# prob.net
KiCad netlist of a schematic drawn in EasyEDA
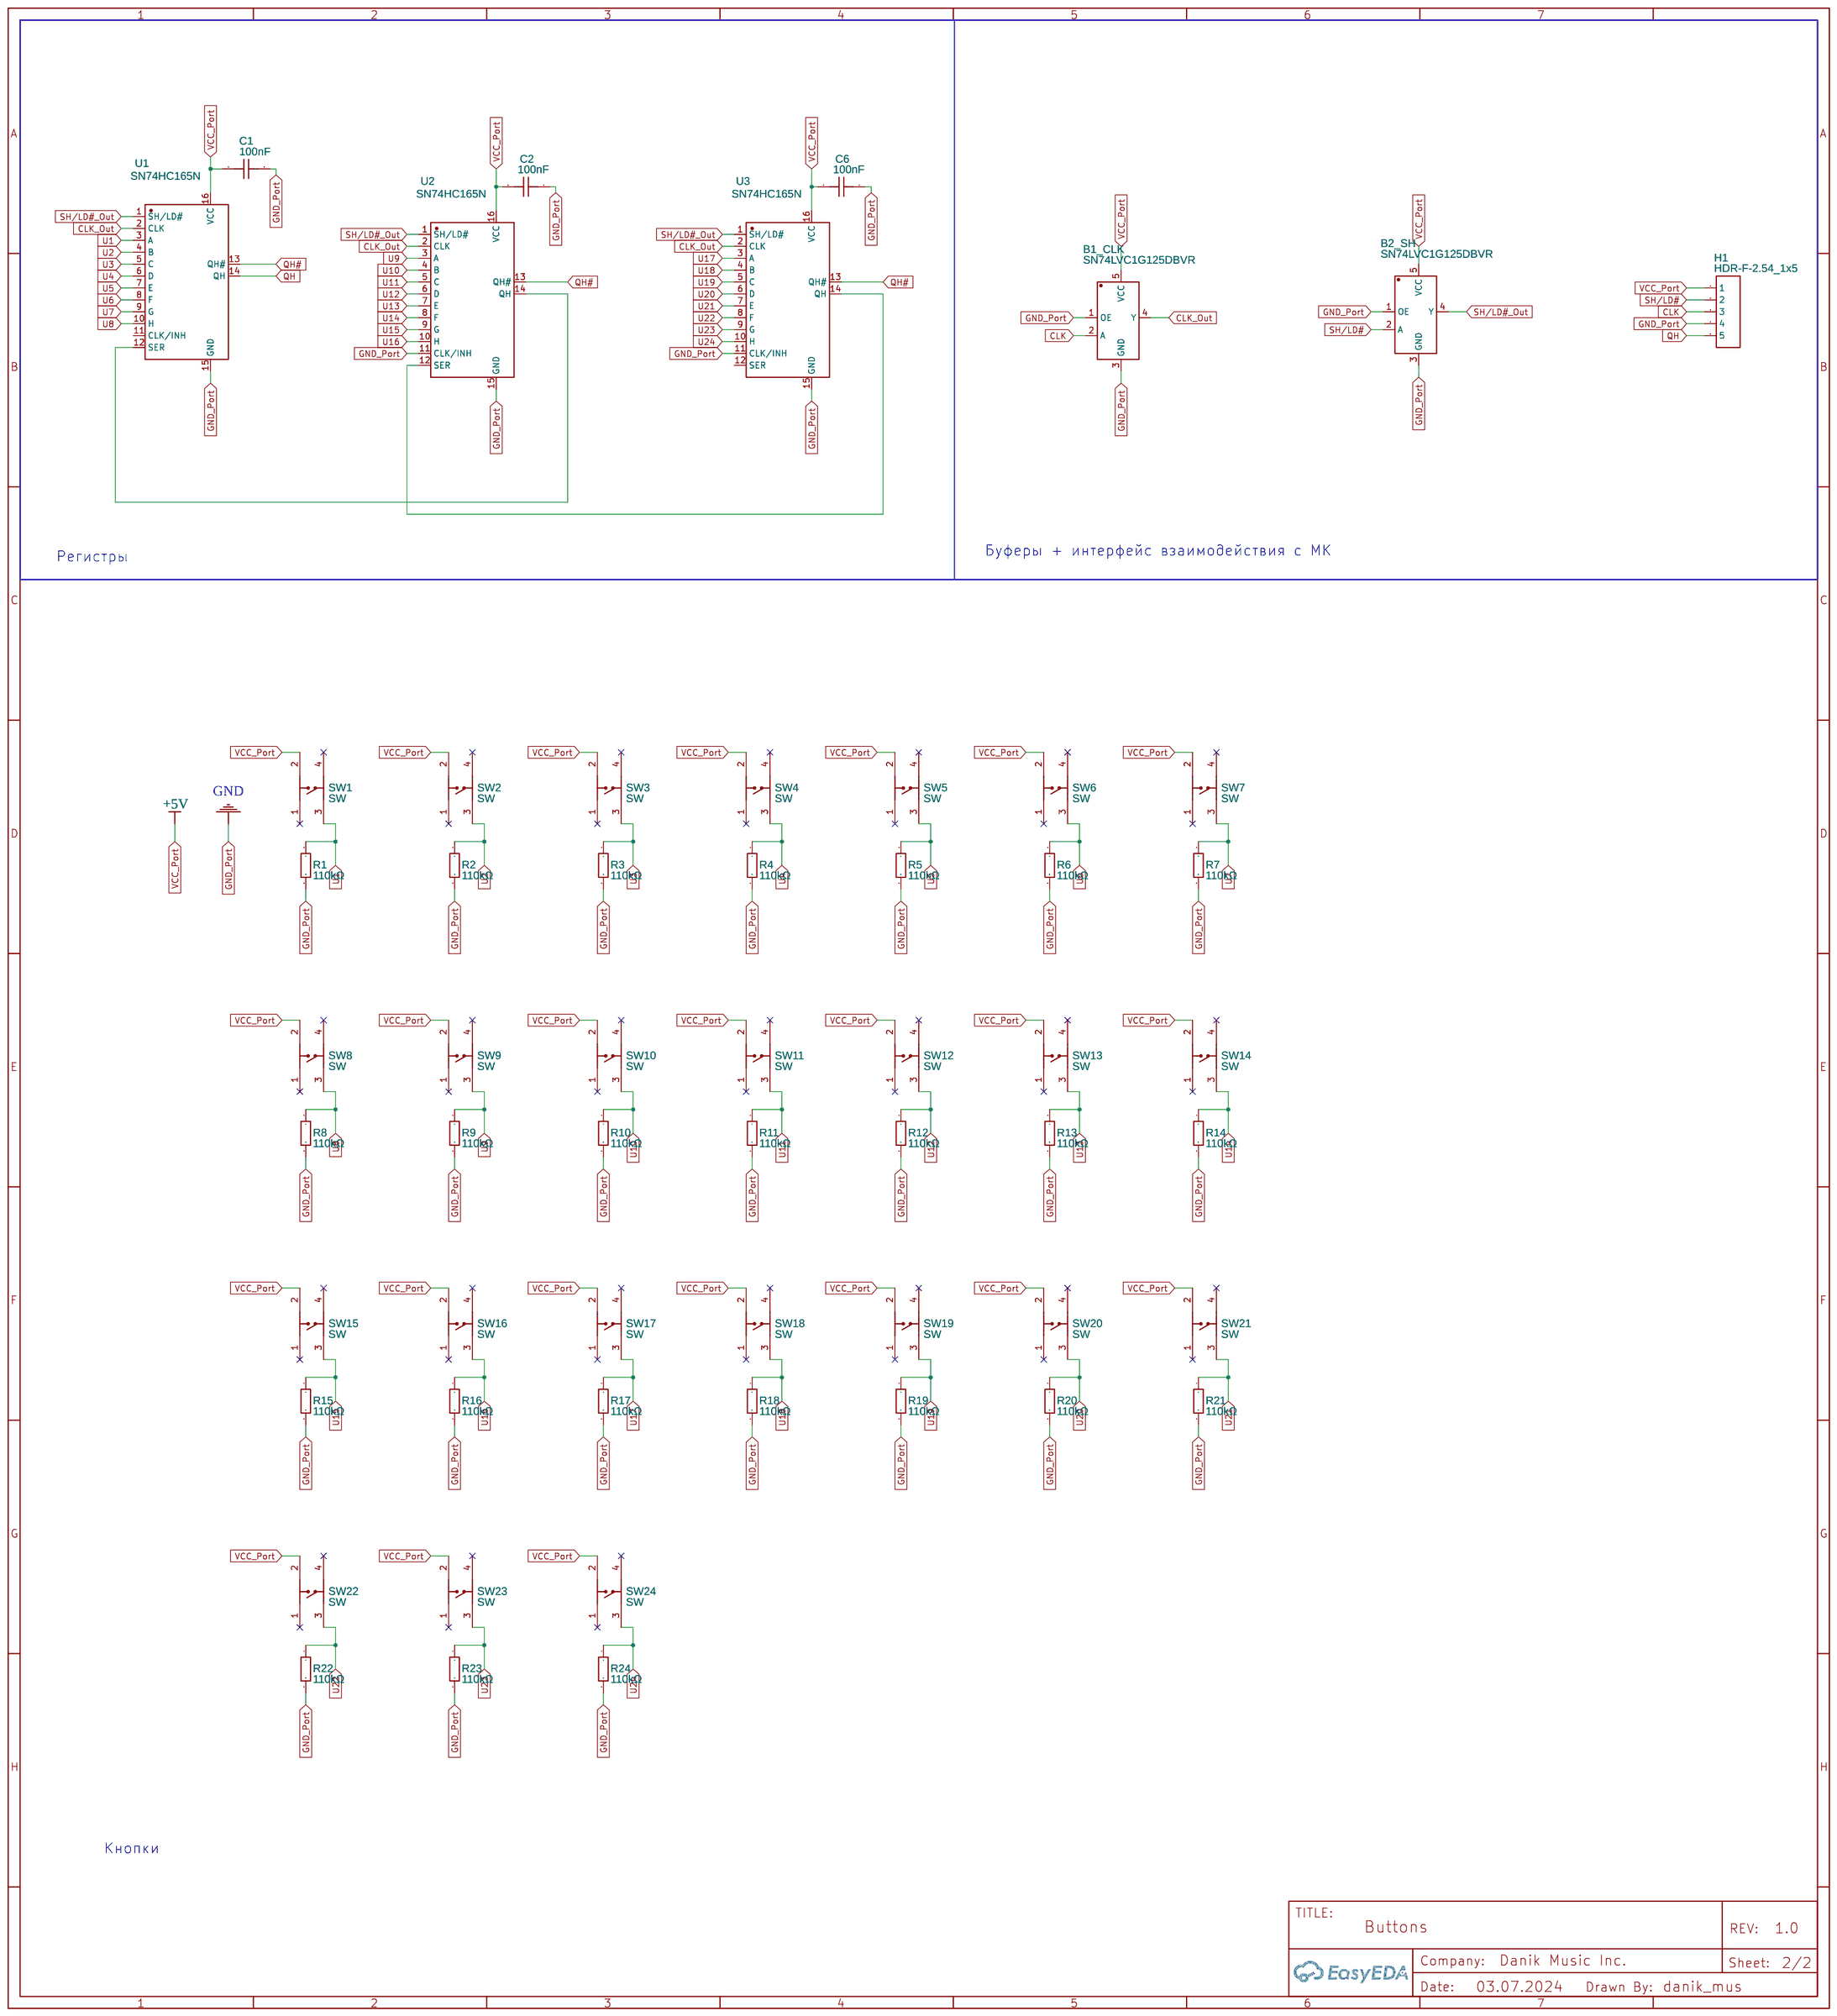
[diagram p0: schematic sheet]

(export (version "E")
  (design (tool "Eeschema 10.0.6"))
  (components
    (comp (ref "B1_CLK")
      (value "SN74LVC1G125DBVR")
      (fields (field (name "Manufacturer") "TI(德州仪器)"))
      (libsource (lib "") (part "SN74LVC1G125DBVR"))
    )
    (comp (ref "B2_SH")
      (value "SN74LVC1G125DBVR")
      (fields (field (name "Manufacturer") "TI(德州仪器)"))
      (libsource (lib "") (part "SN74LVC1G125DBVR_1"))
    )
    (comp (ref "C1")
      (value "100nF")
      (fields (field (name "Manufacturer Part") "PE104J2A0504") (field (name "Manufacturer") "KYET(科雅)"))
      (libsource (lib "") (part "PE104J2A0504_1"))
    )
    (comp (ref "C2")
      (value "100nF")
      (fields (field (name "Manufacturer Part") "PE104J2A0504") (field (name "Manufacturer") "KYET(科雅)"))
      (libsource (lib "") (part "PE104J2A0504"))
    )
    (comp (ref "C6")
      (value "100nF")
      (fields (field (name "Manufacturer Part") "PE104J2A0504") (field (name "Manufacturer") "KYET(科雅)"))
      (libsource (lib "") (part "PE104J2A0504"))
    )
    (comp (ref "H1") (value "HDR-F-2.54_1x5") (libsource (lib "") (part "HDR-F-2.54_1x5")))
    (comp (ref "R1")
      (value "110kΩ")
      (fields
        (field (name "Manufacturer Part") "CF1/4W-110KΩ±5% T52")
        (field (name "Manufacturer") "CCO(千志电子)")
      )
      (libsource (lib "") (part "CF1/4W-110KΩ±5% T52"))
    )
    (comp (ref "R2")
      (value "110kΩ")
      (fields
        (field (name "Manufacturer Part") "CF1/4W-110KΩ±5% T52")
        (field (name "Manufacturer") "CCO(千志电子)")
      )
      (libsource (lib "") (part "CF1/4W-110KΩ±5% T52"))
    )
    (comp (ref "R3")
      (value "110kΩ")
      (fields
        (field (name "Manufacturer Part") "CF1/4W-110KΩ±5% T52")
        (field (name "Manufacturer") "CCO(千志电子)")
      )
      (libsource (lib "") (part "CF1/4W-110KΩ±5% T52"))
    )
    (comp (ref "R4")
      (value "110kΩ")
      (fields
        (field (name "Manufacturer Part") "CF1/4W-110KΩ±5% T52")
        (field (name "Manufacturer") "CCO(千志电子)")
      )
      (libsource (lib "") (part "CF1/4W-110KΩ±5% T52"))
    )
    (comp (ref "R5")
      (value "110kΩ")
      (fields
        (field (name "Manufacturer Part") "CF1/4W-110KΩ±5% T52")
        (field (name "Manufacturer") "CCO(千志电子)")
      )
      (libsource (lib "") (part "CF1/4W-110KΩ±5% T52"))
    )
    (comp (ref "R6")
      (value "110kΩ")
      (fields
        (field (name "Manufacturer Part") "CF1/4W-110KΩ±5% T52")
        (field (name "Manufacturer") "CCO(千志电子)")
      )
      (libsource (lib "") (part "CF1/4W-110KΩ±5% T52"))
    )
    (comp (ref "R7")
      (value "110kΩ")
      (fields
        (field (name "Manufacturer Part") "CF1/4W-110KΩ±5% T52")
        (field (name "Manufacturer") "CCO(千志电子)")
      )
      (libsource (lib "") (part "CF1/4W-110KΩ±5% T52"))
    )
    (comp (ref "R8")
      (value "110kΩ")
      (fields
        (field (name "Manufacturer Part") "CF1/4W-110KΩ±5% T52")
        (field (name "Manufacturer") "CCO(千志电子)")
      )
      (libsource (lib "") (part "CF1/4W-110KΩ±5% T52"))
    )
    (comp (ref "R9")
      (value "110kΩ")
      (fields
        (field (name "Manufacturer Part") "CF1/4W-110KΩ±5% T52")
        (field (name "Manufacturer") "CCO(千志电子)")
      )
      (libsource (lib "") (part "CF1/4W-110KΩ±5% T52"))
    )
    (comp (ref "R10")
      (value "110kΩ")
      (fields
        (field (name "Manufacturer Part") "CF1/4W-110KΩ±5% T52")
        (field (name "Manufacturer") "CCO(千志电子)")
      )
      (libsource (lib "") (part "CF1/4W-110KΩ±5% T52"))
    )
    (comp (ref "R11")
      (value "110kΩ")
      (fields
        (field (name "Manufacturer Part") "CF1/4W-110KΩ±5% T52")
        (field (name "Manufacturer") "CCO(千志电子)")
      )
      (libsource (lib "") (part "CF1/4W-110KΩ±5% T52"))
    )
    (comp (ref "R12")
      (value "110kΩ")
      (fields
        (field (name "Manufacturer Part") "CF1/4W-110KΩ±5% T52")
        (field (name "Manufacturer") "CCO(千志电子)")
      )
      (libsource (lib "") (part "CF1/4W-110KΩ±5% T52"))
    )
    (comp (ref "R13")
      (value "110kΩ")
      (fields
        (field (name "Manufacturer Part") "CF1/4W-110KΩ±5% T52")
        (field (name "Manufacturer") "CCO(千志电子)")
      )
      (libsource (lib "") (part "CF1/4W-110KΩ±5% T52"))
    )
    (comp (ref "R14")
      (value "110kΩ")
      (fields
        (field (name "Manufacturer Part") "CF1/4W-110KΩ±5% T52")
        (field (name "Manufacturer") "CCO(千志电子)")
      )
      (libsource (lib "") (part "CF1/4W-110KΩ±5% T52"))
    )
    (comp (ref "R15")
      (value "110kΩ")
      (fields
        (field (name "Manufacturer Part") "CF1/4W-110KΩ±5% T52")
        (field (name "Manufacturer") "CCO(千志电子)")
      )
      (libsource (lib "") (part "CF1/4W-110KΩ±5% T52"))
    )
    (comp (ref "R16")
      (value "110kΩ")
      (fields
        (field (name "Manufacturer Part") "CF1/4W-110KΩ±5% T52")
        (field (name "Manufacturer") "CCO(千志电子)")
      )
      (libsource (lib "") (part "CF1/4W-110KΩ±5% T52"))
    )
    (comp (ref "R17")
      (value "110kΩ")
      (fields
        (field (name "Manufacturer Part") "CF1/4W-110KΩ±5% T52")
        (field (name "Manufacturer") "CCO(千志电子)")
      )
      (libsource (lib "") (part "CF1/4W-110KΩ±5% T52"))
    )
    (comp (ref "R18")
      (value "110kΩ")
      (fields
        (field (name "Manufacturer Part") "CF1/4W-110KΩ±5% T52")
        (field (name "Manufacturer") "CCO(千志电子)")
      )
      (libsource (lib "") (part "CF1/4W-110KΩ±5% T52"))
    )
    (comp (ref "R19")
      (value "110kΩ")
      (fields
        (field (name "Manufacturer Part") "CF1/4W-110KΩ±5% T52")
        (field (name "Manufacturer") "CCO(千志电子)")
      )
      (libsource (lib "") (part "CF1/4W-110KΩ±5% T52"))
    )
    (comp (ref "R20")
      (value "110kΩ")
      (fields
        (field (name "Manufacturer Part") "CF1/4W-110KΩ±5% T52")
        (field (name "Manufacturer") "CCO(千志电子)")
      )
      (libsource (lib "") (part "CF1/4W-110KΩ±5% T52"))
    )
    (comp (ref "R21")
      (value "110kΩ")
      (fields
        (field (name "Manufacturer Part") "CF1/4W-110KΩ±5% T52")
        (field (name "Manufacturer") "CCO(千志电子)")
      )
      (libsource (lib "") (part "CF1/4W-110KΩ±5% T52"))
    )
    (comp (ref "R22")
      (value "110kΩ")
      (fields
        (field (name "Manufacturer Part") "CF1/4W-110KΩ±5% T52")
        (field (name "Manufacturer") "CCO(千志电子)")
      )
      (libsource (lib "") (part "CF1/4W-110KΩ±5% T52"))
    )
    (comp (ref "R23")
      (value "110kΩ")
      (fields
        (field (name "Manufacturer Part") "CF1/4W-110KΩ±5% T52")
        (field (name "Manufacturer") "CCO(千志电子)")
      )
      (libsource (lib "") (part "CF1/4W-110KΩ±5% T52"))
    )
    (comp (ref "R24")
      (value "110kΩ")
      (fields
        (field (name "Manufacturer Part") "CF1/4W-110KΩ±5% T52")
        (field (name "Manufacturer") "CCO(千志电子)")
      )
      (libsource (lib "") (part "CF1/4W-110KΩ±5% T52"))
    )
    (comp (ref "SW1")
      (value "SW")
      (fields (field (name "Manufacturer Part") "按键"))
      (libsource (lib "") (part "SW"))
    )
    (comp (ref "SW2")
      (value "SW")
      (fields (field (name "Manufacturer Part") "按键"))
      (libsource (lib "") (part "SW"))
    )
    (comp (ref "SW3")
      (value "SW")
      (fields (field (name "Manufacturer Part") "按键"))
      (libsource (lib "") (part "SW"))
    )
    (comp (ref "SW4")
      (value "SW")
      (fields (field (name "Manufacturer Part") "按键"))
      (libsource (lib "") (part "SW"))
    )
    (comp (ref "SW5")
      (value "SW")
      (fields (field (name "Manufacturer Part") "按键"))
      (libsource (lib "") (part "SW"))
    )
    (comp (ref "SW6")
      (value "SW")
      (fields (field (name "Manufacturer Part") "按键"))
      (libsource (lib "") (part "SW"))
    )
    (comp (ref "SW7")
      (value "SW")
      (fields (field (name "Manufacturer Part") "按键"))
      (libsource (lib "") (part "SW"))
    )
    (comp (ref "SW8")
      (value "SW")
      (fields (field (name "Manufacturer Part") "按键"))
      (libsource (lib "") (part "SW"))
    )
    (comp (ref "SW9")
      (value "SW")
      (fields (field (name "Manufacturer Part") "按键"))
      (libsource (lib "") (part "SW"))
    )
    (comp (ref "SW10")
      (value "SW")
      (fields (field (name "Manufacturer Part") "按键"))
      (libsource (lib "") (part "SW"))
    )
    (comp (ref "SW11")
      (value "SW")
      (fields (field (name "Manufacturer Part") "按键"))
      (libsource (lib "") (part "SW"))
    )
    (comp (ref "SW12")
      (value "SW")
      (fields (field (name "Manufacturer Part") "按键"))
      (libsource (lib "") (part "SW"))
    )
    (comp (ref "SW13")
      (value "SW")
      (fields (field (name "Manufacturer Part") "按键"))
      (libsource (lib "") (part "SW"))
    )
    (comp (ref "SW14")
      (value "SW")
      (fields (field (name "Manufacturer Part") "按键"))
      (libsource (lib "") (part "SW"))
    )
    (comp (ref "SW15")
      (value "SW")
      (fields (field (name "Manufacturer Part") "按键"))
      (libsource (lib "") (part "SW"))
    )
    (comp (ref "SW16")
      (value "SW")
      (fields (field (name "Manufacturer Part") "按键"))
      (libsource (lib "") (part "SW"))
    )
    (comp (ref "SW17")
      (value "SW")
      (fields (field (name "Manufacturer Part") "按键"))
      (libsource (lib "") (part "SW"))
    )
    (comp (ref "SW18")
      (value "SW")
      (fields (field (name "Manufacturer Part") "按键"))
      (libsource (lib "") (part "SW"))
    )
    (comp (ref "SW19")
      (value "SW")
      (fields (field (name "Manufacturer Part") "按键"))
      (libsource (lib "") (part "SW"))
    )
    (comp (ref "SW20")
      (value "SW")
      (fields (field (name "Manufacturer Part") "按键"))
      (libsource (lib "") (part "SW"))
    )
    (comp (ref "SW21")
      (value "SW")
      (fields (field (name "Manufacturer Part") "按键"))
      (libsource (lib "") (part "SW"))
    )
    (comp (ref "SW22")
      (value "SW")
      (fields (field (name "Manufacturer Part") "按键"))
      (libsource (lib "") (part "SW"))
    )
    (comp (ref "SW23")
      (value "SW")
      (fields (field (name "Manufacturer Part") "按键"))
      (libsource (lib "") (part "SW"))
    )
    (comp (ref "SW24")
      (value "SW")
      (fields (field (name "Manufacturer Part") "按键"))
      (libsource (lib "") (part "SW"))
    )
    (comp (ref "U1")
      (value "SN74HC165N")
      (fields (field (name "Manufacturer") "TI(德州仪器)"))
      (libsource (lib "") (part "SN74HC165N"))
    )
    (comp (ref "U2")
      (value "SN74HC165N")
      (fields (field (name "Manufacturer") "TI(德州仪器)"))
      (libsource (lib "") (part "SN74HC165N"))
    )
    (comp (ref "U3")
      (value "SN74HC165N")
      (fields (field (name "Manufacturer") "TI(德州仪器)"))
      (libsource (lib "") (part "SN74HC165N"))
    )
  )
  (nets
    (net (code "1") (name "CLK") (class "Default")
      (node (ref "B1_CLK") (pin "2") (pinfunction "A_2") (pintype "unspecified"))
      (node (ref "H1") (pin "3") (pinfunction "3_3") (pintype "unspecified"))
    )
    (net (code "2") (name "CLK_Out") (class "Default")
      (node (ref "B1_CLK") (pin "4") (pinfunction "Y_4") (pintype "unspecified"))
      (node (ref "U1") (pin "2") (pinfunction "CLK_2") (pintype "unspecified"))
      (node (ref "U2") (pin "2") (pinfunction "CLK_2") (pintype "unspecified"))
      (node (ref "U3") (pin "2") (pinfunction "CLK_2") (pintype "unspecified"))
    )
    (net (code "3") (name "GND_Port") (class "Default")
      (node (ref "B1_CLK") (pin "1") (pinfunction "OE_1") (pintype "unspecified"))
      (node (ref "B1_CLK") (pin "3") (pinfunction "GND_3") (pintype "unspecified"))
      (node (ref "B2_SH") (pin "1") (pinfunction "OE_1") (pintype "unspecified"))
      (node (ref "B2_SH") (pin "3") (pinfunction "GND_3") (pintype "unspecified"))
      (node (ref "C1") (pin "2") (pinfunction "2_2") (pintype "unspecified"))
      (node (ref "C2") (pin "1") (pinfunction "1_1") (pintype "unspecified"))
      (node (ref "C6") (pin "1") (pinfunction "1_1") (pintype "unspecified"))
      (node (ref "H1") (pin "4") (pinfunction "4_4") (pintype "unspecified"))
      (node (ref "R1") (pin "2") (pinfunction "2_2") (pintype "unspecified"))
      (node (ref "R10") (pin "2") (pinfunction "2_2") (pintype "unspecified"))
      (node (ref "R11") (pin "2") (pinfunction "2_2") (pintype "unspecified"))
      (node (ref "R12") (pin "2") (pinfunction "2_2") (pintype "unspecified"))
      (node (ref "R13") (pin "2") (pinfunction "2_2") (pintype "unspecified"))
      (node (ref "R14") (pin "2") (pinfunction "2_2") (pintype "unspecified"))
      (node (ref "R15") (pin "2") (pinfunction "2_2") (pintype "unspecified"))
      (node (ref "R16") (pin "2") (pinfunction "2_2") (pintype "unspecified"))
      (node (ref "R17") (pin "2") (pinfunction "2_2") (pintype "unspecified"))
      (node (ref "R18") (pin "2") (pinfunction "2_2") (pintype "unspecified"))
      (node (ref "R19") (pin "2") (pinfunction "2_2") (pintype "unspecified"))
      (node (ref "R2") (pin "2") (pinfunction "2_2") (pintype "unspecified"))
      (node (ref "R20") (pin "2") (pinfunction "2_2") (pintype "unspecified"))
      (node (ref "R21") (pin "2") (pinfunction "2_2") (pintype "unspecified"))
      (node (ref "R22") (pin "2") (pinfunction "2_2") (pintype "unspecified"))
      (node (ref "R23") (pin "2") (pinfunction "2_2") (pintype "unspecified"))
      (node (ref "R24") (pin "2") (pinfunction "2_2") (pintype "unspecified"))
      (node (ref "R3") (pin "2") (pinfunction "2_2") (pintype "unspecified"))
      (node (ref "R4") (pin "2") (pinfunction "2_2") (pintype "unspecified"))
      (node (ref "R5") (pin "2") (pinfunction "2_2") (pintype "unspecified"))
      (node (ref "R6") (pin "2") (pinfunction "2_2") (pintype "unspecified"))
      (node (ref "R7") (pin "2") (pinfunction "2_2") (pintype "unspecified"))
      (node (ref "R8") (pin "2") (pinfunction "2_2") (pintype "unspecified"))
      (node (ref "R9") (pin "2") (pinfunction "2_2") (pintype "unspecified"))
      (node (ref "U1") (pin "15") (pinfunction "GND_15") (pintype "unspecified"))
      (node (ref "U2") (pin "11") (pinfunction "CLK/INH_11") (pintype "unspecified"))
      (node (ref "U2") (pin "15") (pinfunction "GND_15") (pintype "unspecified"))
      (node (ref "U3") (pin "11") (pinfunction "CLK/INH_11") (pintype "unspecified"))
      (node (ref "U3") (pin "15") (pinfunction "GND_15") (pintype "unspecified"))
    )
    (net (code "4") (name "Net-(U1-SER)") (class "Default")
      (node (ref "U1") (pin "12") (pinfunction "SER_12") (pintype "unspecified"))
      (node (ref "U2") (pin "14") (pinfunction "QH_14") (pintype "unspecified"))
    )
    (net (code "5") (name "Net-(U2-SER)") (class "Default")
      (node (ref "U2") (pin "12") (pinfunction "SER_12") (pintype "unspecified"))
      (node (ref "U3") (pin "14") (pinfunction "QH_14") (pintype "unspecified"))
    )
    (net (code "6") (name "QH") (class "Default")
      (node (ref "H1") (pin "5") (pinfunction "5_5") (pintype "unspecified"))
      (node (ref "U1") (pin "14") (pinfunction "QH_14") (pintype "unspecified"))
    )
    (net (code "7") (name "QH#") (class "Default")
      (node (ref "U1") (pin "13") (pinfunction "QH#_13") (pintype "unspecified"))
      (node (ref "U2") (pin "13") (pinfunction "QH#_13") (pintype "unspecified"))
      (node (ref "U3") (pin "13") (pinfunction "QH#_13") (pintype "unspecified"))
    )
    (net (code "8") (name "SH{slash}LD#") (class "Default")
      (node (ref "B2_SH") (pin "2") (pinfunction "A_2") (pintype "unspecified"))
      (node (ref "H1") (pin "2") (pinfunction "2_2") (pintype "unspecified"))
    )
    (net (code "9") (name "SH{slash}LD#_Out") (class "Default")
      (node (ref "B2_SH") (pin "4") (pinfunction "Y_4") (pintype "unspecified"))
      (node (ref "U1") (pin "1") (pinfunction "SH/LD#_1") (pintype "unspecified"))
      (node (ref "U2") (pin "1") (pinfunction "SH/LD#_1") (pintype "unspecified"))
      (node (ref "U3") (pin "1") (pinfunction "SH/LD#_1") (pintype "unspecified"))
    )
    (net (code "10") (name "U1") (class "Default")
      (node (ref "R1") (pin "1") (pinfunction "1_1") (pintype "unspecified"))
      (node (ref "SW1") (pin "3") (pinfunction "3_3") (pintype "unspecified"))
      (node (ref "U1") (pin "3") (pinfunction "A_3") (pintype "unspecified"))
    )
    (net (code "11") (name "U2") (class "Default")
      (node (ref "R2") (pin "1") (pinfunction "1_1") (pintype "unspecified"))
      (node (ref "SW2") (pin "3") (pinfunction "3_3") (pintype "unspecified"))
      (node (ref "U1") (pin "4") (pinfunction "B_4") (pintype "unspecified"))
    )
    (net (code "12") (name "U3") (class "Default")
      (node (ref "R3") (pin "1") (pinfunction "1_1") (pintype "unspecified"))
      (node (ref "SW3") (pin "3") (pinfunction "3_3") (pintype "unspecified"))
      (node (ref "U1") (pin "5") (pinfunction "C_5") (pintype "unspecified"))
    )
    (net (code "13") (name "U4") (class "Default")
      (node (ref "R4") (pin "1") (pinfunction "1_1") (pintype "unspecified"))
      (node (ref "SW4") (pin "3") (pinfunction "3_3") (pintype "unspecified"))
      (node (ref "U1") (pin "6") (pinfunction "D_6") (pintype "unspecified"))
    )
    (net (code "14") (name "U5") (class "Default")
      (node (ref "R5") (pin "1") (pinfunction "1_1") (pintype "unspecified"))
      (node (ref "SW5") (pin "3") (pinfunction "3_3") (pintype "unspecified"))
      (node (ref "U1") (pin "7") (pinfunction "E_7") (pintype "unspecified"))
    )
    (net (code "15") (name "U6") (class "Default")
      (node (ref "R6") (pin "1") (pinfunction "1_1") (pintype "unspecified"))
      (node (ref "SW6") (pin "3") (pinfunction "3_3") (pintype "unspecified"))
      (node (ref "U1") (pin "8") (pinfunction "F_8") (pintype "unspecified"))
    )
    (net (code "16") (name "U7") (class "Default")
      (node (ref "R7") (pin "1") (pinfunction "1_1") (pintype "unspecified"))
      (node (ref "SW7") (pin "3") (pinfunction "3_3") (pintype "unspecified"))
      (node (ref "U1") (pin "9") (pinfunction "G_9") (pintype "unspecified"))
    )
    (net (code "17") (name "U8") (class "Default")
      (node (ref "R8") (pin "1") (pinfunction "1_1") (pintype "unspecified"))
      (node (ref "SW8") (pin "3") (pinfunction "3_3") (pintype "unspecified"))
      (node (ref "U1") (pin "10") (pinfunction "H_10") (pintype "unspecified"))
    )
    (net (code "18") (name "U9") (class "Default")
      (node (ref "R9") (pin "1") (pinfunction "1_1") (pintype "unspecified"))
      (node (ref "SW9") (pin "3") (pinfunction "3_3") (pintype "unspecified"))
      (node (ref "U2") (pin "3") (pinfunction "A_3") (pintype "unspecified"))
    )
    (net (code "19") (name "U10") (class "Default")
      (node (ref "R10") (pin "1") (pinfunction "1_1") (pintype "unspecified"))
      (node (ref "SW10") (pin "3") (pinfunction "3_3") (pintype "unspecified"))
      (node (ref "U2") (pin "4") (pinfunction "B_4") (pintype "unspecified"))
    )
    (net (code "20") (name "U11") (class "Default")
      (node (ref "R11") (pin "1") (pinfunction "1_1") (pintype "unspecified"))
      (node (ref "SW11") (pin "3") (pinfunction "3_3") (pintype "unspecified"))
      (node (ref "U2") (pin "5") (pinfunction "C_5") (pintype "unspecified"))
    )
    (net (code "21") (name "U12") (class "Default")
      (node (ref "R12") (pin "1") (pinfunction "1_1") (pintype "unspecified"))
      (node (ref "SW12") (pin "3") (pinfunction "3_3") (pintype "unspecified"))
      (node (ref "U2") (pin "6") (pinfunction "D_6") (pintype "unspecified"))
    )
    (net (code "22") (name "U13") (class "Default")
      (node (ref "R13") (pin "1") (pinfunction "1_1") (pintype "unspecified"))
      (node (ref "SW13") (pin "3") (pinfunction "3_3") (pintype "unspecified"))
      (node (ref "U2") (pin "7") (pinfunction "E_7") (pintype "unspecified"))
    )
    (net (code "23") (name "U14") (class "Default")
      (node (ref "R14") (pin "1") (pinfunction "1_1") (pintype "unspecified"))
      (node (ref "SW14") (pin "3") (pinfunction "3_3") (pintype "unspecified"))
      (node (ref "U2") (pin "8") (pinfunction "F_8") (pintype "unspecified"))
    )
    (net (code "24") (name "U15") (class "Default")
      (node (ref "R15") (pin "1") (pinfunction "1_1") (pintype "unspecified"))
      (node (ref "SW15") (pin "3") (pinfunction "3_3") (pintype "unspecified"))
      (node (ref "U2") (pin "9") (pinfunction "G_9") (pintype "unspecified"))
    )
    (net (code "25") (name "U16") (class "Default")
      (node (ref "R16") (pin "1") (pinfunction "1_1") (pintype "unspecified"))
      (node (ref "SW16") (pin "3") (pinfunction "3_3") (pintype "unspecified"))
      (node (ref "U2") (pin "10") (pinfunction "H_10") (pintype "unspecified"))
    )
    (net (code "26") (name "U17") (class "Default")
      (node (ref "R17") (pin "1") (pinfunction "1_1") (pintype "unspecified"))
      (node (ref "SW17") (pin "3") (pinfunction "3_3") (pintype "unspecified"))
      (node (ref "U3") (pin "3") (pinfunction "A_3") (pintype "unspecified"))
    )
    (net (code "27") (name "U18") (class "Default")
      (node (ref "R18") (pin "1") (pinfunction "1_1") (pintype "unspecified"))
      (node (ref "SW18") (pin "3") (pinfunction "3_3") (pintype "unspecified"))
      (node (ref "U3") (pin "4") (pinfunction "B_4") (pintype "unspecified"))
    )
    (net (code "28") (name "U19") (class "Default")
      (node (ref "R19") (pin "1") (pinfunction "1_1") (pintype "unspecified"))
      (node (ref "SW19") (pin "3") (pinfunction "3_3") (pintype "unspecified"))
      (node (ref "U3") (pin "5") (pinfunction "C_5") (pintype "unspecified"))
    )
    (net (code "29") (name "U20") (class "Default")
      (node (ref "R20") (pin "1") (pinfunction "1_1") (pintype "unspecified"))
      (node (ref "SW20") (pin "3") (pinfunction "3_3") (pintype "unspecified"))
      (node (ref "U3") (pin "6") (pinfunction "D_6") (pintype "unspecified"))
    )
    (net (code "30") (name "U21") (class "Default")
      (node (ref "R21") (pin "1") (pinfunction "1_1") (pintype "unspecified"))
      (node (ref "SW21") (pin "3") (pinfunction "3_3") (pintype "unspecified"))
      (node (ref "U3") (pin "7") (pinfunction "E_7") (pintype "unspecified"))
    )
    (net (code "31") (name "U22") (class "Default")
      (node (ref "R22") (pin "1") (pinfunction "1_1") (pintype "unspecified"))
      (node (ref "SW22") (pin "3") (pinfunction "3_3") (pintype "unspecified"))
      (node (ref "U3") (pin "8") (pinfunction "F_8") (pintype "unspecified"))
    )
    (net (code "32") (name "U23") (class "Default")
      (node (ref "R23") (pin "1") (pinfunction "1_1") (pintype "unspecified"))
      (node (ref "SW23") (pin "3") (pinfunction "3_3") (pintype "unspecified"))
      (node (ref "U3") (pin "9") (pinfunction "G_9") (pintype "unspecified"))
    )
    (net (code "33") (name "U24") (class "Default")
      (node (ref "R24") (pin "1") (pinfunction "1_1") (pintype "unspecified"))
      (node (ref "SW24") (pin "3") (pinfunction "3_3") (pintype "unspecified"))
      (node (ref "U3") (pin "10") (pinfunction "H_10") (pintype "unspecified"))
    )
    (net (code "34") (name "VCC_Port") (class "Default")
      (node (ref "B1_CLK") (pin "5") (pinfunction "VCC_5") (pintype "unspecified"))
      (node (ref "B2_SH") (pin "5") (pinfunction "VCC_5") (pintype "unspecified"))
      (node (ref "C1") (pin "1") (pinfunction "1_1") (pintype "unspecified"))
      (node (ref "C2") (pin "2") (pinfunction "2_2") (pintype "unspecified"))
      (node (ref "C6") (pin "2") (pinfunction "2_2") (pintype "unspecified"))
      (node (ref "H1") (pin "1") (pinfunction "1_1") (pintype "unspecified"))
      (node (ref "SW1") (pin "2") (pinfunction "2_2") (pintype "unspecified"))
      (node (ref "SW10") (pin "2") (pinfunction "2_2") (pintype "unspecified"))
      (node (ref "SW11") (pin "2") (pinfunction "2_2") (pintype "unspecified"))
      (node (ref "SW12") (pin "2") (pinfunction "2_2") (pintype "unspecified"))
      (node (ref "SW13") (pin "2") (pinfunction "2_2") (pintype "unspecified"))
      (node (ref "SW14") (pin "2") (pinfunction "2_2") (pintype "unspecified"))
      (node (ref "SW15") (pin "2") (pinfunction "2_2") (pintype "unspecified"))
      (node (ref "SW16") (pin "2") (pinfunction "2_2") (pintype "unspecified"))
      (node (ref "SW17") (pin "2") (pinfunction "2_2") (pintype "unspecified"))
      (node (ref "SW18") (pin "2") (pinfunction "2_2") (pintype "unspecified"))
      (node (ref "SW19") (pin "2") (pinfunction "2_2") (pintype "unspecified"))
      (node (ref "SW2") (pin "2") (pinfunction "2_2") (pintype "unspecified"))
      (node (ref "SW20") (pin "2") (pinfunction "2_2") (pintype "unspecified"))
      (node (ref "SW21") (pin "2") (pinfunction "2_2") (pintype "unspecified"))
      (node (ref "SW22") (pin "2") (pinfunction "2_2") (pintype "unspecified"))
      (node (ref "SW23") (pin "2") (pinfunction "2_2") (pintype "unspecified"))
      (node (ref "SW24") (pin "2") (pinfunction "2_2") (pintype "unspecified"))
      (node (ref "SW3") (pin "2") (pinfunction "2_2") (pintype "unspecified"))
      (node (ref "SW4") (pin "2") (pinfunction "2_2") (pintype "unspecified"))
      (node (ref "SW5") (pin "2") (pinfunction "2_2") (pintype "unspecified"))
      (node (ref "SW6") (pin "2") (pinfunction "2_2") (pintype "unspecified"))
      (node (ref "SW7") (pin "2") (pinfunction "2_2") (pintype "unspecified"))
      (node (ref "SW8") (pin "2") (pinfunction "2_2") (pintype "unspecified"))
      (node (ref "SW9") (pin "2") (pinfunction "2_2") (pintype "unspecified"))
      (node (ref "U1") (pin "16") (pinfunction "VCC_16") (pintype "unspecified"))
      (node (ref "U2") (pin "16") (pinfunction "VCC_16") (pintype "unspecified"))
      (node (ref "U3") (pin "16") (pinfunction "VCC_16") (pintype "unspecified"))
    )
    (net (code "35") (name "unconnected-(SW1-Pad1)") (class "Default")
      (node (ref "SW1") (pin "1") (pinfunction "1_1") (pintype "unspecified+no_connect"))
    )
    (net (code "36") (name "unconnected-(SW1-Pad4)") (class "Default")
      (node (ref "SW1") (pin "4") (pinfunction "4_4") (pintype "unspecified+no_connect"))
    )
    (net (code "37") (name "unconnected-(SW2-Pad1)") (class "Default")
      (node (ref "SW2") (pin "1") (pinfunction "1_1") (pintype "unspecified+no_connect"))
    )
    (net (code "38") (name "unconnected-(SW2-Pad4)") (class "Default")
      (node (ref "SW2") (pin "4") (pinfunction "4_4") (pintype "unspecified+no_connect"))
    )
    (net (code "39") (name "unconnected-(SW3-Pad1)") (class "Default")
      (node (ref "SW3") (pin "1") (pinfunction "1_1") (pintype "unspecified+no_connect"))
    )
    (net (code "40") (name "unconnected-(SW3-Pad4)") (class "Default")
      (node (ref "SW3") (pin "4") (pinfunction "4_4") (pintype "unspecified+no_connect"))
    )
    (net (code "41") (name "unconnected-(SW4-Pad1)") (class "Default")
      (node (ref "SW4") (pin "1") (pinfunction "1_1") (pintype "unspecified+no_connect"))
    )
    (net (code "42") (name "unconnected-(SW4-Pad4)") (class "Default")
      (node (ref "SW4") (pin "4") (pinfunction "4_4") (pintype "unspecified+no_connect"))
    )
    (net (code "43") (name "unconnected-(SW5-Pad1)") (class "Default")
      (node (ref "SW5") (pin "1") (pinfunction "1_1") (pintype "unspecified+no_connect"))
    )
    (net (code "44") (name "unconnected-(SW5-Pad4)") (class "Default")
      (node (ref "SW5") (pin "4") (pinfunction "4_4") (pintype "unspecified+no_connect"))
    )
    (net (code "45") (name "unconnected-(SW6-Pad1)") (class "Default")
      (node (ref "SW6") (pin "1") (pinfunction "1_1") (pintype "unspecified+no_connect"))
    )
    (net (code "46") (name "unconnected-(SW6-Pad4)") (class "Default")
      (node (ref "SW6") (pin "4") (pinfunction "4_4") (pintype "unspecified+no_connect"))
    )
    (net (code "47") (name "unconnected-(SW7-Pad1)") (class "Default")
      (node (ref "SW7") (pin "1") (pinfunction "1_1") (pintype "unspecified+no_connect"))
    )
    (net (code "48") (name "unconnected-(SW7-Pad4)") (class "Default")
      (node (ref "SW7") (pin "4") (pinfunction "4_4") (pintype "unspecified+no_connect"))
    )
    (net (code "49") (name "unconnected-(SW8-Pad1)") (class "Default")
      (node (ref "SW8") (pin "1") (pinfunction "1_1") (pintype "unspecified+no_connect"))
    )
    (net (code "50") (name "unconnected-(SW8-Pad4)") (class "Default")
      (node (ref "SW8") (pin "4") (pinfunction "4_4") (pintype "unspecified+no_connect"))
    )
    (net (code "51") (name "unconnected-(SW9-Pad1)") (class "Default")
      (node (ref "SW9") (pin "1") (pinfunction "1_1") (pintype "unspecified+no_connect"))
    )
    (net (code "52") (name "unconnected-(SW9-Pad4)") (class "Default")
      (node (ref "SW9") (pin "4") (pinfunction "4_4") (pintype "unspecified+no_connect"))
    )
    (net (code "53") (name "unconnected-(SW10-Pad1)") (class "Default")
      (node (ref "SW10") (pin "1") (pinfunction "1_1") (pintype "unspecified+no_connect"))
    )
    (net (code "54") (name "unconnected-(SW10-Pad4)") (class "Default")
      (node (ref "SW10") (pin "4") (pinfunction "4_4") (pintype "unspecified+no_connect"))
    )
    (net (code "55") (name "unconnected-(SW11-Pad1)") (class "Default")
      (node (ref "SW11") (pin "1") (pinfunction "1_1") (pintype "unspecified+no_connect"))
    )
    (net (code "56") (name "unconnected-(SW11-Pad4)") (class "Default")
      (node (ref "SW11") (pin "4") (pinfunction "4_4") (pintype "unspecified+no_connect"))
    )
    (net (code "57") (name "unconnected-(SW12-Pad1)") (class "Default")
      (node (ref "SW12") (pin "1") (pinfunction "1_1") (pintype "unspecified+no_connect"))
    )
    (net (code "58") (name "unconnected-(SW12-Pad4)") (class "Default")
      (node (ref "SW12") (pin "4") (pinfunction "4_4") (pintype "unspecified+no_connect"))
    )
    (net (code "59") (name "unconnected-(SW13-Pad1)") (class "Default")
      (node (ref "SW13") (pin "1") (pinfunction "1_1") (pintype "unspecified+no_connect"))
    )
    (net (code "60") (name "unconnected-(SW13-Pad4)") (class "Default")
      (node (ref "SW13") (pin "4") (pinfunction "4_4") (pintype "unspecified+no_connect"))
    )
    (net (code "61") (name "unconnected-(SW14-Pad1)") (class "Default")
      (node (ref "SW14") (pin "1") (pinfunction "1_1") (pintype "unspecified+no_connect"))
    )
    (net (code "62") (name "unconnected-(SW14-Pad4)") (class "Default")
      (node (ref "SW14") (pin "4") (pinfunction "4_4") (pintype "unspecified+no_connect"))
    )
    (net (code "63") (name "unconnected-(SW15-Pad1)") (class "Default")
      (node (ref "SW15") (pin "1") (pinfunction "1_1") (pintype "unspecified+no_connect"))
    )
    (net (code "64") (name "unconnected-(SW15-Pad4)") (class "Default")
      (node (ref "SW15") (pin "4") (pinfunction "4_4") (pintype "unspecified+no_connect"))
    )
    (net (code "65") (name "unconnected-(SW16-Pad1)") (class "Default")
      (node (ref "SW16") (pin "1") (pinfunction "1_1") (pintype "unspecified+no_connect"))
    )
    (net (code "66") (name "unconnected-(SW16-Pad4)") (class "Default")
      (node (ref "SW16") (pin "4") (pinfunction "4_4") (pintype "unspecified+no_connect"))
    )
    (net (code "67") (name "unconnected-(SW17-Pad1)") (class "Default")
      (node (ref "SW17") (pin "1") (pinfunction "1_1") (pintype "unspecified+no_connect"))
    )
    (net (code "68") (name "unconnected-(SW17-Pad4)") (class "Default")
      (node (ref "SW17") (pin "4") (pinfunction "4_4") (pintype "unspecified+no_connect"))
    )
    (net (code "69") (name "unconnected-(SW18-Pad1)") (class "Default")
      (node (ref "SW18") (pin "1") (pinfunction "1_1") (pintype "unspecified+no_connect"))
    )
    (net (code "70") (name "unconnected-(SW18-Pad4)") (class "Default")
      (node (ref "SW18") (pin "4") (pinfunction "4_4") (pintype "unspecified+no_connect"))
    )
    (net (code "71") (name "unconnected-(SW19-Pad1)") (class "Default")
      (node (ref "SW19") (pin "1") (pinfunction "1_1") (pintype "unspecified+no_connect"))
    )
    (net (code "72") (name "unconnected-(SW19-Pad4)") (class "Default")
      (node (ref "SW19") (pin "4") (pinfunction "4_4") (pintype "unspecified+no_connect"))
    )
    (net (code "73") (name "unconnected-(SW20-Pad1)") (class "Default")
      (node (ref "SW20") (pin "1") (pinfunction "1_1") (pintype "unspecified+no_connect"))
    )
    (net (code "74") (name "unconnected-(SW20-Pad4)") (class "Default")
      (node (ref "SW20") (pin "4") (pinfunction "4_4") (pintype "unspecified+no_connect"))
    )
    (net (code "75") (name "unconnected-(SW21-Pad1)") (class "Default")
      (node (ref "SW21") (pin "1") (pinfunction "1_1") (pintype "unspecified+no_connect"))
    )
    (net (code "76") (name "unconnected-(SW21-Pad4)") (class "Default")
      (node (ref "SW21") (pin "4") (pinfunction "4_4") (pintype "unspecified+no_connect"))
    )
    (net (code "77") (name "unconnected-(SW22-Pad1)") (class "Default")
      (node (ref "SW22") (pin "1") (pinfunction "1_1") (pintype "unspecified+no_connect"))
    )
    (net (code "78") (name "unconnected-(SW22-Pad4)") (class "Default")
      (node (ref "SW22") (pin "4") (pinfunction "4_4") (pintype "unspecified+no_connect"))
    )
    (net (code "79") (name "unconnected-(SW23-Pad1)") (class "Default")
      (node (ref "SW23") (pin "1") (pinfunction "1_1") (pintype "unspecified+no_connect"))
    )
    (net (code "80") (name "unconnected-(SW23-Pad4)") (class "Default")
      (node (ref "SW23") (pin "4") (pinfunction "4_4") (pintype "unspecified+no_connect"))
    )
    (net (code "81") (name "unconnected-(SW24-Pad1)") (class "Default")
      (node (ref "SW24") (pin "1") (pinfunction "1_1") (pintype "unspecified+no_connect"))
    )
    (net (code "82") (name "unconnected-(SW24-Pad4)") (class "Default")
      (node (ref "SW24") (pin "4") (pinfunction "4_4") (pintype "unspecified+no_connect"))
    )
    (net (code "83") (name "unconnected-(U1-CLK{slash}INH-Pad11)") (class "Default")
      (node (ref "U1") (pin "11") (pinfunction "CLK/INH_11") (pintype "unspecified"))
    )
    (net (code "84") (name "unconnected-(U3-SER-Pad12)") (class "Default")
      (node (ref "U3") (pin "12") (pinfunction "SER_12") (pintype "unspecified"))
    )
  )
)
